# cs301_Group2.net
KiCad netlist of a schematic drawn in Altium Designer
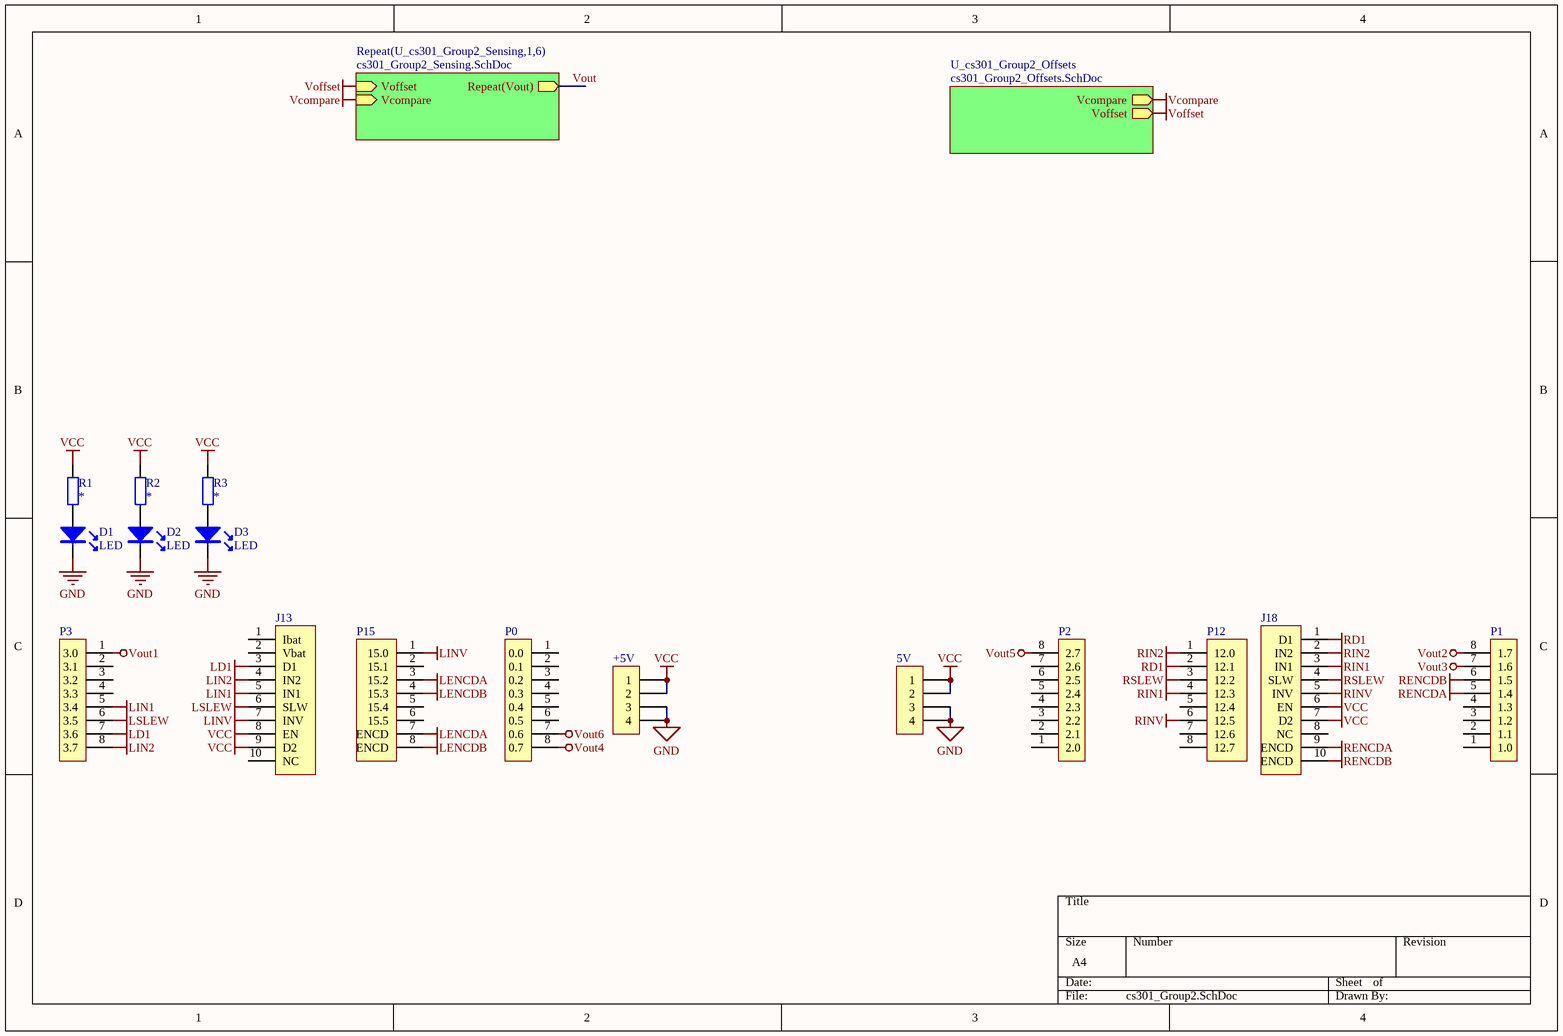
[diagram p0: cs301_Group2.SchDoc]

(export (version "E")
  (design (tool "Eeschema 10.0.6"))
  (components
    (comp (ref "+5V")
      (value "5V")
      (footprint "IDC4")
      (description "Connector")
      (libsource (lib "Miscellaneous Devices") (part "CON4"))
    )
    (comp (ref "5V")
      (value "5V")
      (footprint "IDC4")
      (description "Connector")
      (libsource (lib "Miscellaneous Devices") (part "CON4"))
    )
    (comp (ref "D1") (value "LED") (footprint "LED0.1/5MM") (libsource (lib "COMSYS301_2013") (part "LED")))
    (comp (ref "D2") (value "LED") (footprint "LED0.1/5MM") (libsource (lib "COMSYS301_2013") (part "LED")))
    (comp (ref "D3") (value "LED") (footprint "LED0.1/5MM") (libsource (lib "COMSYS301_2013") (part "LED")))
    (comp (ref "J13")
      (value "CON10")
      (footprint "idc10")
      (description "Connector")
      (libsource (lib "") (part "CON10_1"))
    )
    (comp (ref "J18")
      (value "CON10")
      (footprint "IDC10")
      (description "Connector")
      (libsource (lib "Miscellaneous Devices") (part "CON10"))
    )
    (comp (ref "P0")
      (value "P0")
      (footprint "idc8")
      (description "Connector")
      (libsource (lib "Miscellaneous Devices") (part "CON8"))
    )
    (comp (ref "P1")
      (value "P1")
      (footprint "idc8")
      (description "Connector")
      (libsource (lib "") (part "CON8_2"))
    )
    (comp (ref "P2")
      (value "P2")
      (footprint "idc8")
      (description "Connector")
      (libsource (lib "") (part "CON8_1"))
    )
    (comp (ref "P3")
      (value "P3")
      (footprint "idc8")
      (description "Connector")
      (libsource (lib "Miscellaneous Devices") (part "CON8"))
    )
    (comp (ref "P12")
      (value "P12")
      (footprint "idc8")
      (description "Connector")
      (libsource (lib "Miscellaneous Devices") (part "CON8_1"))
    )
    (comp (ref "P15")
      (value "P15")
      (footprint "idc8")
      (description "Connector")
      (libsource (lib "") (part "CON8_1_1"))
    )
    (comp (ref "R1")
      (value "*")
      (footprint "0805 RES")
      (description "0805 resistor")
      (fields (field (name "PUBLISHER") "Altium Limited"))
      (libsource (lib "EE209_Library") (part "Res_SMT_0805"))
    )
    (comp (ref "R2")
      (value "*")
      (footprint "0805 RES")
      (description "0805 resistor")
      (fields (field (name "PUBLISHER") "Altium Limited"))
      (libsource (lib "EE209_Library") (part "Res_SMT_0805"))
    )
    (comp (ref "R3")
      (value "*")
      (footprint "0805 RES")
      (description "0805 resistor")
      (fields (field (name "PUBLISHER") "Altium Limited"))
      (libsource (lib "EE209_Library") (part "Res_SMT_0805"))
    )
  )
  (nets
    (net (code "2") (name "GND") (class "Default")
      (node (ref "+5V") (pin "3") (pinfunction "3_3") (pintype "passive"))
      (node (ref "+5V") (pin "4") (pinfunction "4_4") (pintype "passive"))
      (node (ref "5V") (pin "3") (pinfunction "3_3") (pintype "passive"))
      (node (ref "5V") (pin "4") (pinfunction "4_4") (pintype "passive"))
      (node (ref "D1") (pin "K") (pinfunction "2_K") (pintype "passive"))
      (node (ref "D2") (pin "K") (pinfunction "2_K") (pintype "passive"))
      (node (ref "D3") (pin "K") (pinfunction "2_K") (pintype "passive"))
    )
    (net (code "3") (name "LD1") (class "Default")
      (node (ref "J13") (pin "3") (pinfunction "D1_3") (pintype "passive"))
      (node (ref "P3") (pin "7") (pinfunction "3.6_7") (pintype "passive"))
    )
    (net (code "4") (name "LENCDA") (class "Default")
      (node (ref "P15") (pin "3") (pinfunction "15.2_3") (pintype "passive"))
      (node (ref "P15") (pin "7") (pinfunction "ENCD_7") (pintype "passive"))
    )
    (net (code "5") (name "LENCDB") (class "Default")
      (node (ref "P15") (pin "4") (pinfunction "15.3_4") (pintype "passive"))
      (node (ref "P15") (pin "8") (pinfunction "ENCD_8") (pintype "passive"))
    )
    (net (code "6") (name "LIN1") (class "Default")
      (node (ref "J13") (pin "5") (pinfunction "IN1_5") (pintype "passive"))
      (node (ref "P3") (pin "5") (pinfunction "3.4_5") (pintype "passive"))
    )
    (net (code "7") (name "LIN2") (class "Default")
      (node (ref "J13") (pin "4") (pinfunction "IN2_4") (pintype "passive"))
      (node (ref "P3") (pin "8") (pinfunction "3.7_8") (pintype "passive"))
    )
    (net (code "8") (name "LINV") (class "Default")
      (node (ref "J13") (pin "7") (pinfunction "INV_7") (pintype "passive"))
      (node (ref "P15") (pin "1") (pinfunction "15.0_1") (pintype "passive"))
    )
    (net (code "9") (name "LSLEW") (class "Default")
      (node (ref "J13") (pin "6") (pinfunction "SLW_6") (pintype "passive"))
      (node (ref "P3") (pin "6") (pinfunction "3.5_6") (pintype "passive"))
    )
    (net (code "10") (name "Net-(D1-1)") (class "Default")
      (node (ref "D1") (pin "A") (pinfunction "1_A") (pintype "passive"))
      (node (ref "R1") (pin "1") (pinfunction "1_1") (pintype "passive"))
    )
    (net (code "11") (name "Net-(D2-1)") (class "Default")
      (node (ref "D2") (pin "A") (pinfunction "1_A") (pintype "passive"))
      (node (ref "R2") (pin "1") (pinfunction "1_1") (pintype "passive"))
    )
    (net (code "12") (name "Net-(D3-1)") (class "Default")
      (node (ref "D3") (pin "A") (pinfunction "1_A") (pintype "passive"))
      (node (ref "R3") (pin "1") (pinfunction "1_1") (pintype "passive"))
    )
    (net (code "13") (name "RD1") (class "Default")
      (node (ref "J18") (pin "1") (pinfunction "D1_1") (pintype "passive"))
      (node (ref "P12") (pin "2") (pinfunction "12.1_2") (pintype "passive"))
    )
    (net (code "14") (name "RENCDA") (class "Default")
      (node (ref "J18") (pin "9") (pinfunction "ENCD_9") (pintype "passive"))
      (node (ref "P1") (pin "5") (pinfunction "1.4_5") (pintype "passive"))
    )
    (net (code "15") (name "RENCDB") (class "Default")
      (node (ref "J18") (pin "10") (pinfunction "ENCD_10") (pintype "passive"))
      (node (ref "P1") (pin "6") (pinfunction "1.5_6") (pintype "passive"))
    )
    (net (code "16") (name "RIN1") (class "Default")
      (node (ref "J18") (pin "3") (pinfunction "IN1_3") (pintype "passive"))
      (node (ref "P12") (pin "4") (pinfunction "12.3_4") (pintype "passive"))
    )
    (net (code "17") (name "RIN2") (class "Default")
      (node (ref "J18") (pin "2") (pinfunction "IN2_2") (pintype "passive"))
      (node (ref "P12") (pin "1") (pinfunction "12.0_1") (pintype "passive"))
    )
    (net (code "18") (name "RINV") (class "Default")
      (node (ref "J18") (pin "5") (pinfunction "INV_5") (pintype "passive"))
      (node (ref "P12") (pin "6") (pinfunction "12.5_6") (pintype "passive"))
    )
    (net (code "19") (name "RSLEW") (class "Default")
      (node (ref "J18") (pin "4") (pinfunction "SLW_4") (pintype "passive"))
      (node (ref "P12") (pin "3") (pinfunction "12.2_3") (pintype "passive"))
    )
    (net (code "20") (name "VCC") (class "Default")
      (node (ref "+5V") (pin "1") (pinfunction "1_1") (pintype "passive"))
      (node (ref "+5V") (pin "2") (pinfunction "2_2") (pintype "passive"))
      (node (ref "5V") (pin "1") (pinfunction "1_1") (pintype "passive"))
      (node (ref "5V") (pin "2") (pinfunction "2_2") (pintype "passive"))
      (node (ref "J13") (pin "8") (pinfunction "EN_8") (pintype "passive"))
      (node (ref "J13") (pin "9") (pinfunction "D2_9") (pintype "passive"))
      (node (ref "J18") (pin "6") (pinfunction "EN_6") (pintype "passive"))
      (node (ref "J18") (pin "7") (pinfunction "D2_7") (pintype "passive"))
      (node (ref "R1") (pin "2") (pinfunction "2_2") (pintype "passive"))
      (node (ref "R2") (pin "2") (pinfunction "2_2") (pintype "passive"))
      (node (ref "R3") (pin "2") (pinfunction "2_2") (pintype "passive"))
    )
    (net (code "23") (name "Vout1") (class "Default")
      (node (ref "P3") (pin "1") (pinfunction "3.0_1") (pintype "passive"))
    )
    (net (code "24") (name "Vout2") (class "Default")
      (node (ref "P1") (pin "8") (pinfunction "1.7_8") (pintype "passive"))
    )
    (net (code "25") (name "Vout3") (class "Default")
      (node (ref "P1") (pin "7") (pinfunction "1.6_7") (pintype "passive"))
    )
    (net (code "26") (name "Vout4") (class "Default")
      (node (ref "P0") (pin "8") (pinfunction "3.7_8") (pintype "passive"))
    )
    (net (code "27") (name "Vout5") (class "Default")
      (node (ref "P2") (pin "8") (pinfunction "2.7_8") (pintype "passive"))
    )
    (net (code "28") (name "Vout6") (class "Default")
      (node (ref "P0") (pin "7") (pinfunction "3.6_7") (pintype "passive"))
    )
    (net (code "29") (name "unconnected-(J13-Ibat-Pad1)") (class "Default")
      (node (ref "J13") (pin "1") (pinfunction "Ibat_1") (pintype "passive"))
    )
    (net (code "30") (name "unconnected-(J13-NC-Pad10)") (class "Default")
      (node (ref "J13") (pin "10") (pinfunction "NC_10") (pintype "passive"))
    )
    (net (code "31") (name "unconnected-(J13-Vbat-Pad2)") (class "Default")
      (node (ref "J13") (pin "2") (pinfunction "Vbat_2") (pintype "passive"))
    )
    (net (code "32") (name "unconnected-(J18-NC-Pad8)") (class "Default")
      (node (ref "J18") (pin "8") (pinfunction "NC_8") (pintype "passive"))
    )
    (net (code "33") (name "unconnected-(P0-3.0-Pad1)") (class "Default")
      (node (ref "P0") (pin "1") (pinfunction "3.0_1") (pintype "passive"))
    )
    (net (code "34") (name "unconnected-(P0-3.1-Pad2)") (class "Default")
      (node (ref "P0") (pin "2") (pinfunction "3.1_2") (pintype "passive"))
    )
    (net (code "35") (name "unconnected-(P0-3.2-Pad3)") (class "Default")
      (node (ref "P0") (pin "3") (pinfunction "3.2_3") (pintype "passive"))
    )
    (net (code "36") (name "unconnected-(P0-3.3-Pad4)") (class "Default")
      (node (ref "P0") (pin "4") (pinfunction "3.3_4") (pintype "passive"))
    )
    (net (code "37") (name "unconnected-(P0-3.4-Pad5)") (class "Default")
      (node (ref "P0") (pin "5") (pinfunction "3.4_5") (pintype "passive"))
    )
    (net (code "38") (name "unconnected-(P0-3.5-Pad6)") (class "Default")
      (node (ref "P0") (pin "6") (pinfunction "3.5_6") (pintype "passive"))
    )
    (net (code "39") (name "unconnected-(P1-1.0-Pad1)") (class "Default")
      (node (ref "P1") (pin "1") (pinfunction "1.0_1") (pintype "passive"))
    )
    (net (code "40") (name "unconnected-(P1-1.1-Pad2)") (class "Default")
      (node (ref "P1") (pin "2") (pinfunction "1.1_2") (pintype "passive"))
    )
    (net (code "41") (name "unconnected-(P1-1.2-Pad3)") (class "Default")
      (node (ref "P1") (pin "3") (pinfunction "1.2_3") (pintype "passive"))
    )
    (net (code "42") (name "unconnected-(P1-1.3-Pad4)") (class "Default")
      (node (ref "P1") (pin "4") (pinfunction "1.3_4") (pintype "passive"))
    )
    (net (code "43") (name "unconnected-(P2-2.0-Pad1)") (class "Default")
      (node (ref "P2") (pin "1") (pinfunction "2.0_1") (pintype "passive"))
    )
    (net (code "44") (name "unconnected-(P2-2.1-Pad2)") (class "Default")
      (node (ref "P2") (pin "2") (pinfunction "2.1_2") (pintype "passive"))
    )
    (net (code "45") (name "unconnected-(P2-2.2-Pad3)") (class "Default")
      (node (ref "P2") (pin "3") (pinfunction "2.2_3") (pintype "passive"))
    )
    (net (code "46") (name "unconnected-(P2-2.3-Pad4)") (class "Default")
      (node (ref "P2") (pin "4") (pinfunction "2.3_4") (pintype "passive"))
    )
    (net (code "47") (name "unconnected-(P2-2.4-Pad5)") (class "Default")
      (node (ref "P2") (pin "5") (pinfunction "2.4_5") (pintype "passive"))
    )
    (net (code "48") (name "unconnected-(P2-2.5-Pad6)") (class "Default")
      (node (ref "P2") (pin "6") (pinfunction "2.5_6") (pintype "passive"))
    )
    (net (code "49") (name "unconnected-(P2-2.6-Pad7)") (class "Default")
      (node (ref "P2") (pin "7") (pinfunction "2.6_7") (pintype "passive"))
    )
    (net (code "50") (name "unconnected-(P3-3.1-Pad2)") (class "Default")
      (node (ref "P3") (pin "2") (pinfunction "3.1_2") (pintype "passive"))
    )
    (net (code "51") (name "unconnected-(P3-3.2-Pad3)") (class "Default")
      (node (ref "P3") (pin "3") (pinfunction "3.2_3") (pintype "passive"))
    )
    (net (code "52") (name "unconnected-(P3-3.3-Pad4)") (class "Default")
      (node (ref "P3") (pin "4") (pinfunction "3.3_4") (pintype "passive"))
    )
    (net (code "53") (name "unconnected-(P12-12.4-Pad5)") (class "Default")
      (node (ref "P12") (pin "5") (pinfunction "12.4_5") (pintype "passive"))
    )
    (net (code "54") (name "unconnected-(P12-12.6-Pad7)") (class "Default")
      (node (ref "P12") (pin "7") (pinfunction "12.6_7") (pintype "passive"))
    )
    (net (code "55") (name "unconnected-(P12-12.7-Pad8)") (class "Default")
      (node (ref "P12") (pin "8") (pinfunction "12.7_8") (pintype "passive"))
    )
    (net (code "56") (name "unconnected-(P15-15.1-Pad2)") (class "Default")
      (node (ref "P15") (pin "2") (pinfunction "15.1_2") (pintype "passive"))
    )
    (net (code "57") (name "unconnected-(P15-15.4-Pad5)") (class "Default")
      (node (ref "P15") (pin "5") (pinfunction "15.4_5") (pintype "passive"))
    )
    (net (code "58") (name "unconnected-(P15-15.5-Pad6)") (class "Default")
      (node (ref "P15") (pin "6") (pinfunction "15.5_6") (pintype "passive"))
    )
  )
)
